# ARM_EURO_Platine7.net
KiCad netlist of a schematic drawn in Altium Designer
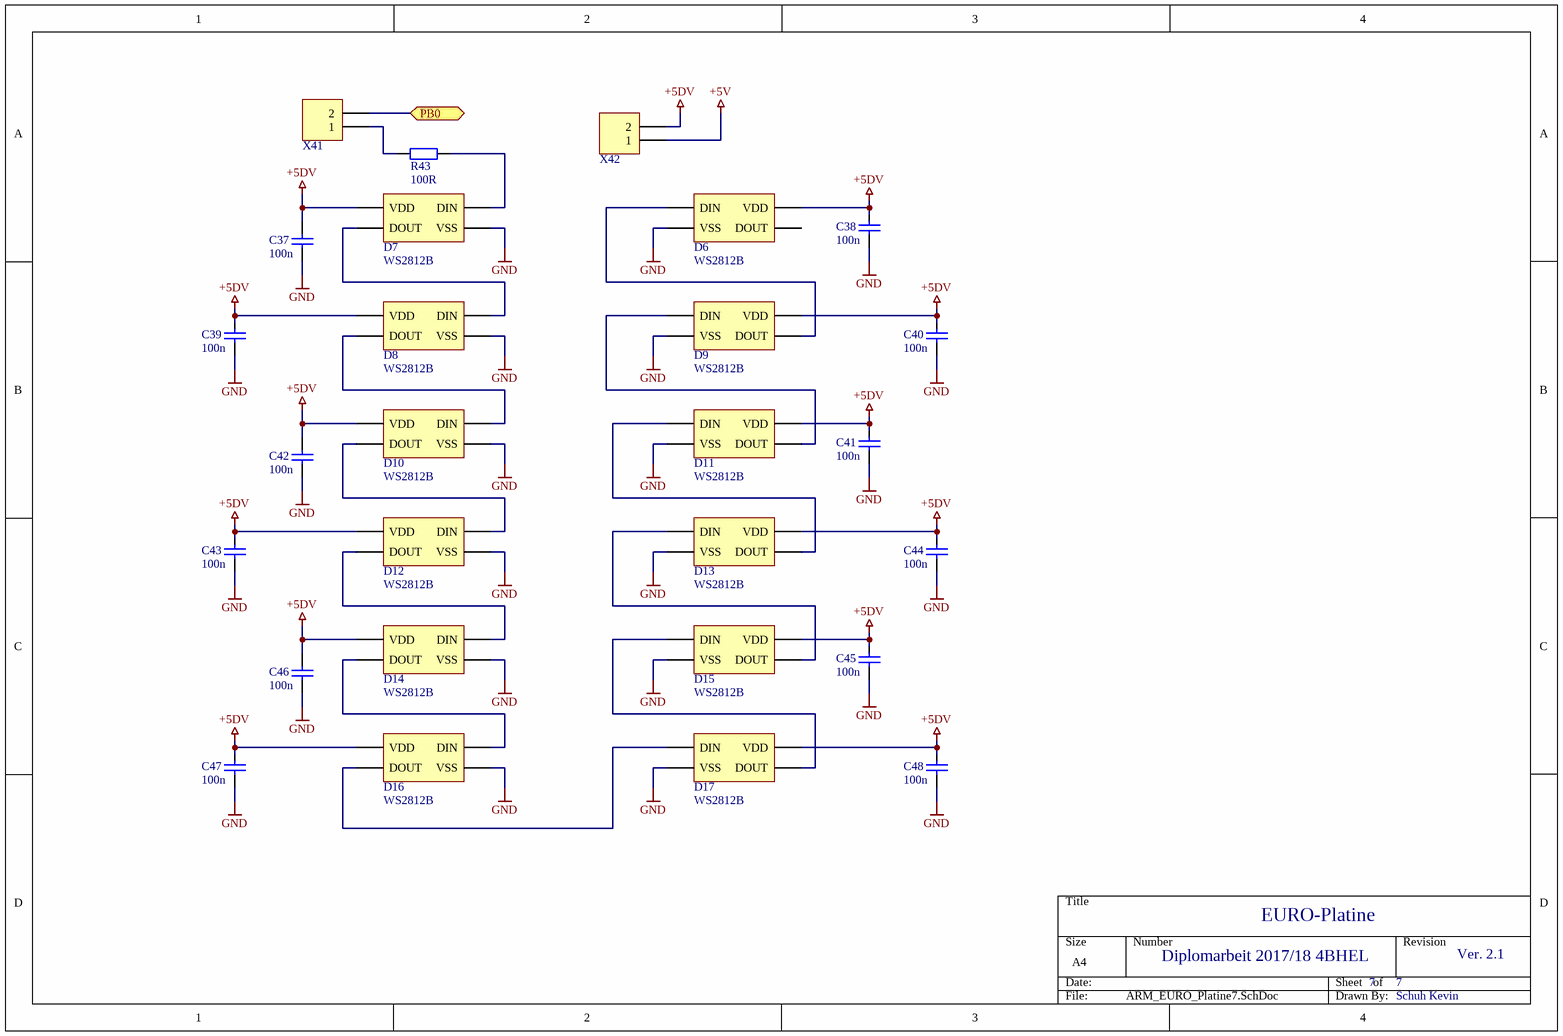
[diagram p0: ARM_EURO_Platine7.SchDoc]

(export (version "E")
  (design (tool "Eeschema 10.0.6"))
  (components
    (comp (ref "C37")
      (value "100n")
      (footprint "0805_CAP")
      (description "Capacitor_SMD")
      (fields (field (name "Comment") "Cap_Keramik_SMD") (field (name "PUBLISHER") "Altium Limited"))
      (libsource (lib "ARM_Libary_EURO") (part "Cap_Keramik_SMD"))
    )
    (comp (ref "C38")
      (value "100n")
      (footprint "0805_CAP")
      (description "Capacitor_SMD")
      (fields (field (name "Comment") "Cap_Keramik_SMD") (field (name "PUBLISHER") "Altium Limited"))
      (libsource (lib "ARM_Libary_EURO") (part "Cap_Keramik_SMD"))
    )
    (comp (ref "C39")
      (value "100n")
      (footprint "0805_CAP")
      (description "Capacitor_SMD")
      (fields (field (name "Comment") "Cap_Keramik_SMD") (field (name "PUBLISHER") "Altium Limited"))
      (libsource (lib "ARM_Libary_EURO") (part "Cap_Keramik_SMD"))
    )
    (comp (ref "C40")
      (value "100n")
      (footprint "0805_CAP")
      (description "Capacitor_SMD")
      (fields (field (name "Comment") "Cap_Keramik_SMD") (field (name "PUBLISHER") "Altium Limited"))
      (libsource (lib "ARM_Libary_EURO") (part "Cap_Keramik_SMD"))
    )
    (comp (ref "C41")
      (value "100n")
      (footprint "0805_CAP")
      (description "Capacitor_SMD")
      (fields (field (name "Comment") "Cap_Keramik_SMD") (field (name "PUBLISHER") "Altium Limited"))
      (libsource (lib "ARM_Libary_EURO") (part "Cap_Keramik_SMD"))
    )
    (comp (ref "C42")
      (value "100n")
      (footprint "0805_CAP")
      (description "Capacitor_SMD")
      (fields (field (name "Comment") "Cap_Keramik_SMD") (field (name "PUBLISHER") "Altium Limited"))
      (libsource (lib "ARM_Libary_EURO") (part "Cap_Keramik_SMD"))
    )
    (comp (ref "C43")
      (value "100n")
      (footprint "0805_CAP")
      (description "Capacitor_SMD")
      (fields (field (name "Comment") "Cap_Keramik_SMD") (field (name "PUBLISHER") "Altium Limited"))
      (libsource (lib "ARM_Libary_EURO") (part "Cap_Keramik_SMD"))
    )
    (comp (ref "C44")
      (value "100n")
      (footprint "0805_CAP")
      (description "Capacitor_SMD")
      (fields (field (name "Comment") "Cap_Keramik_SMD") (field (name "PUBLISHER") "Altium Limited"))
      (libsource (lib "ARM_Libary_EURO") (part "Cap_Keramik_SMD"))
    )
    (comp (ref "C45")
      (value "100n")
      (footprint "0805_CAP")
      (description "Capacitor_SMD")
      (fields (field (name "Comment") "Cap_Keramik_SMD") (field (name "PUBLISHER") "Altium Limited"))
      (libsource (lib "ARM_Libary_EURO") (part "Cap_Keramik_SMD"))
    )
    (comp (ref "C46")
      (value "100n")
      (footprint "0805_CAP")
      (description "Capacitor_SMD")
      (fields (field (name "Comment") "Cap_Keramik_SMD") (field (name "PUBLISHER") "Altium Limited"))
      (libsource (lib "ARM_Libary_EURO") (part "Cap_Keramik_SMD"))
    )
    (comp (ref "C47")
      (value "100n")
      (footprint "0805_CAP")
      (description "Capacitor_SMD")
      (fields (field (name "Comment") "Cap_Keramik_SMD") (field (name "PUBLISHER") "Altium Limited"))
      (libsource (lib "ARM_Libary_EURO") (part "Cap_Keramik_SMD"))
    )
    (comp (ref "C48")
      (value "100n")
      (footprint "0805_CAP")
      (description "Capacitor_SMD")
      (fields (field (name "Comment") "Cap_Keramik_SMD") (field (name "PUBLISHER") "Altium Limited"))
      (libsource (lib "ARM_Libary_EURO") (part "Cap_Keramik_SMD"))
    )
    (comp (ref "D6")
      (value "WS2812B")
      (footprint "WS2812B")
      (fields (field (name "PUBLISHER") "Altium Limited"))
      (libsource (lib "") (part "WS2812B_1"))
    )
    (comp (ref "D7")
      (value "WS2812B")
      (footprint "WS2812B")
      (fields (field (name "PUBLISHER") "Altium Limited"))
      (libsource (lib "ARM_Libary_EURO") (part "WS2812B"))
    )
    (comp (ref "D8")
      (value "WS2812B")
      (footprint "WS2812B")
      (fields (field (name "PUBLISHER") "Altium Limited"))
      (libsource (lib "ARM_Libary_EURO") (part "WS2812B"))
    )
    (comp (ref "D9")
      (value "WS2812B")
      (footprint "WS2812B")
      (fields (field (name "PUBLISHER") "Altium Limited"))
      (libsource (lib "") (part "WS2812B_1"))
    )
    (comp (ref "D10")
      (value "WS2812B")
      (footprint "WS2812B")
      (fields (field (name "PUBLISHER") "Altium Limited"))
      (libsource (lib "ARM_Libary_EURO") (part "WS2812B"))
    )
    (comp (ref "D11")
      (value "WS2812B")
      (footprint "WS2812B")
      (fields (field (name "PUBLISHER") "Altium Limited"))
      (libsource (lib "") (part "WS2812B_1"))
    )
    (comp (ref "D12")
      (value "WS2812B")
      (footprint "WS2812B")
      (fields (field (name "PUBLISHER") "Altium Limited"))
      (libsource (lib "ARM_Libary_EURO") (part "WS2812B"))
    )
    (comp (ref "D13")
      (value "WS2812B")
      (footprint "WS2812B")
      (fields (field (name "PUBLISHER") "Altium Limited"))
      (libsource (lib "") (part "WS2812B_1"))
    )
    (comp (ref "D14")
      (value "WS2812B")
      (footprint "WS2812B")
      (fields (field (name "PUBLISHER") "Altium Limited"))
      (libsource (lib "ARM_Libary_EURO") (part "WS2812B"))
    )
    (comp (ref "D15")
      (value "WS2812B")
      (footprint "WS2812B")
      (fields (field (name "PUBLISHER") "Altium Limited"))
      (libsource (lib "") (part "WS2812B_1"))
    )
    (comp (ref "D16")
      (value "WS2812B")
      (footprint "WS2812B")
      (fields (field (name "PUBLISHER") "Altium Limited"))
      (libsource (lib "ARM_Libary_EURO") (part "WS2812B"))
    )
    (comp (ref "D17")
      (value "WS2812B")
      (footprint "WS2812B")
      (fields (field (name "PUBLISHER") "Altium Limited"))
      (libsource (lib "") (part "WS2812B_1"))
    )
    (comp (ref "R43")
      (value "100R")
      (footprint "0805_Res")
      (description "Resistor")
      (fields (field (name "Comment") "Res_SMD") (field (name "PUBLISHER") "Altium Limited"))
      (libsource (lib "ARM_Libary_EURO") (part "Res_SMD"))
    )
    (comp (ref "X41")
      (value "Header")
      (footprint "HDR1X2")
      (description "Header, 2-Pin")
      (fields (field (name "PUBLISHER") "Altium Limited"))
      (libsource (lib "ARM_Libary_EURO") (part "Header_2"))
    )
    (comp (ref "X42")
      (value "Header")
      (footprint "HDR1X2")
      (description "Header, 2-Pin")
      (fields (field (name "PUBLISHER") "Altium Limited"))
      (libsource (lib "ARM_Libary_EURO") (part "Header_2"))
    )
  )
  (nets
    (net (code "1") (name "+5DV") (class "Default")
      (node (ref "C37") (pin "2") (pinfunction "2_2") (pintype "passive"))
      (node (ref "C38") (pin "2") (pinfunction "2_2") (pintype "passive"))
      (node (ref "C39") (pin "2") (pinfunction "2_2") (pintype "passive"))
      (node (ref "C40") (pin "2") (pinfunction "2_2") (pintype "passive"))
      (node (ref "C41") (pin "2") (pinfunction "2_2") (pintype "passive"))
      (node (ref "C42") (pin "2") (pinfunction "2_2") (pintype "passive"))
      (node (ref "C43") (pin "2") (pinfunction "2_2") (pintype "passive"))
      (node (ref "C44") (pin "2") (pinfunction "2_2") (pintype "passive"))
      (node (ref "C45") (pin "2") (pinfunction "2_2") (pintype "passive"))
      (node (ref "C46") (pin "2") (pinfunction "2_2") (pintype "passive"))
      (node (ref "C47") (pin "2") (pinfunction "2_2") (pintype "passive"))
      (node (ref "C48") (pin "2") (pinfunction "2_2") (pintype "passive"))
      (node (ref "D10") (pin "1") (pinfunction "VDD_1") (pintype "passive"))
      (node (ref "D11") (pin "1") (pinfunction "VDD_1") (pintype "passive"))
      (node (ref "D12") (pin "1") (pinfunction "VDD_1") (pintype "passive"))
      (node (ref "D13") (pin "1") (pinfunction "VDD_1") (pintype "passive"))
      (node (ref "D14") (pin "1") (pinfunction "VDD_1") (pintype "passive"))
      (node (ref "D15") (pin "1") (pinfunction "VDD_1") (pintype "passive"))
      (node (ref "D16") (pin "1") (pinfunction "VDD_1") (pintype "passive"))
      (node (ref "D17") (pin "1") (pinfunction "VDD_1") (pintype "passive"))
      (node (ref "D6") (pin "1") (pinfunction "VDD_1") (pintype "passive"))
      (node (ref "D7") (pin "1") (pinfunction "VDD_1") (pintype "passive"))
      (node (ref "D8") (pin "1") (pinfunction "VDD_1") (pintype "passive"))
      (node (ref "D9") (pin "1") (pinfunction "VDD_1") (pintype "passive"))
      (node (ref "X42") (pin "2") (pinfunction "2_2") (pintype "passive"))
    )
    (net (code "2") (name "+5V") (class "Default")
      (node (ref "X42") (pin "1") (pinfunction "1_1") (pintype "passive"))
    )
    (net (code "3") (name "/PB0") (class "Default")
      (node (ref "X41") (pin "2") (pinfunction "2_2") (pintype "passive"))
    )
    (net (code "4") (name "GND") (class "Default")
      (node (ref "C37") (pin "1") (pinfunction "1_1") (pintype "passive"))
      (node (ref "C38") (pin "1") (pinfunction "1_1") (pintype "passive"))
      (node (ref "C39") (pin "1") (pinfunction "1_1") (pintype "passive"))
      (node (ref "C40") (pin "1") (pinfunction "1_1") (pintype "passive"))
      (node (ref "C41") (pin "1") (pinfunction "1_1") (pintype "passive"))
      (node (ref "C42") (pin "1") (pinfunction "1_1") (pintype "passive"))
      (node (ref "C43") (pin "1") (pinfunction "1_1") (pintype "passive"))
      (node (ref "C44") (pin "1") (pinfunction "1_1") (pintype "passive"))
      (node (ref "C45") (pin "1") (pinfunction "1_1") (pintype "passive"))
      (node (ref "C46") (pin "1") (pinfunction "1_1") (pintype "passive"))
      (node (ref "C47") (pin "1") (pinfunction "1_1") (pintype "passive"))
      (node (ref "C48") (pin "1") (pinfunction "1_1") (pintype "passive"))
      (node (ref "D10") (pin "3") (pinfunction "VSS_3") (pintype "passive"))
      (node (ref "D11") (pin "3") (pinfunction "VSS_3") (pintype "passive"))
      (node (ref "D12") (pin "3") (pinfunction "VSS_3") (pintype "passive"))
      (node (ref "D13") (pin "3") (pinfunction "VSS_3") (pintype "passive"))
      (node (ref "D14") (pin "3") (pinfunction "VSS_3") (pintype "passive"))
      (node (ref "D15") (pin "3") (pinfunction "VSS_3") (pintype "passive"))
      (node (ref "D16") (pin "3") (pinfunction "VSS_3") (pintype "passive"))
      (node (ref "D17") (pin "3") (pinfunction "VSS_3") (pintype "passive"))
      (node (ref "D6") (pin "3") (pinfunction "VSS_3") (pintype "passive"))
      (node (ref "D7") (pin "3") (pinfunction "VSS_3") (pintype "passive"))
      (node (ref "D8") (pin "3") (pinfunction "VSS_3") (pintype "passive"))
      (node (ref "D9") (pin "3") (pinfunction "VSS_3") (pintype "passive"))
    )
    (net (code "5") (name "Net-(D6-DIN)") (class "Default")
      (node (ref "D6") (pin "4") (pinfunction "DIN_4") (pintype "passive"))
      (node (ref "D9") (pin "2") (pinfunction "DOUT_2") (pintype "passive"))
    )
    (net (code "6") (name "Net-(D7-DIN)") (class "Default")
      (node (ref "D7") (pin "4") (pinfunction "DIN_4") (pintype "passive"))
      (node (ref "R43") (pin "2") (pinfunction "2_2") (pintype "passive"))
    )
    (net (code "7") (name "Net-(D7-DOUT)") (class "Default")
      (node (ref "D7") (pin "2") (pinfunction "DOUT_2") (pintype "passive"))
      (node (ref "D8") (pin "4") (pinfunction "DIN_4") (pintype "passive"))
    )
    (net (code "8") (name "Net-(D10-DIN)") (class "Default")
      (node (ref "D10") (pin "4") (pinfunction "DIN_4") (pintype "passive"))
      (node (ref "D8") (pin "2") (pinfunction "DOUT_2") (pintype "passive"))
    )
    (net (code "9") (name "Net-(D10-DOUT)") (class "Default")
      (node (ref "D10") (pin "2") (pinfunction "DOUT_2") (pintype "passive"))
      (node (ref "D12") (pin "4") (pinfunction "DIN_4") (pintype "passive"))
    )
    (net (code "10") (name "Net-(D11-DIN)") (class "Default")
      (node (ref "D11") (pin "4") (pinfunction "DIN_4") (pintype "passive"))
      (node (ref "D13") (pin "2") (pinfunction "DOUT_2") (pintype "passive"))
    )
    (net (code "11") (name "Net-(D11-DOUT)") (class "Default")
      (node (ref "D11") (pin "2") (pinfunction "DOUT_2") (pintype "passive"))
      (node (ref "D9") (pin "4") (pinfunction "DIN_4") (pintype "passive"))
    )
    (net (code "12") (name "Net-(D12-DOUT)") (class "Default")
      (node (ref "D12") (pin "2") (pinfunction "DOUT_2") (pintype "passive"))
      (node (ref "D14") (pin "4") (pinfunction "DIN_4") (pintype "passive"))
    )
    (net (code "13") (name "Net-(D13-DIN)") (class "Default")
      (node (ref "D13") (pin "4") (pinfunction "DIN_4") (pintype "passive"))
      (node (ref "D15") (pin "2") (pinfunction "DOUT_2") (pintype "passive"))
    )
    (net (code "14") (name "Net-(D14-DOUT)") (class "Default")
      (node (ref "D14") (pin "2") (pinfunction "DOUT_2") (pintype "passive"))
      (node (ref "D16") (pin "4") (pinfunction "DIN_4") (pintype "passive"))
    )
    (net (code "15") (name "Net-(D15-DIN)") (class "Default")
      (node (ref "D15") (pin "4") (pinfunction "DIN_4") (pintype "passive"))
      (node (ref "D17") (pin "2") (pinfunction "DOUT_2") (pintype "passive"))
    )
    (net (code "16") (name "Net-(D16-DOUT)") (class "Default")
      (node (ref "D16") (pin "2") (pinfunction "DOUT_2") (pintype "passive"))
      (node (ref "D17") (pin "4") (pinfunction "DIN_4") (pintype "passive"))
    )
    (net (code "17") (name "Net-(R43-Pad1)") (class "Default")
      (node (ref "R43") (pin "1") (pinfunction "1_1") (pintype "passive"))
      (node (ref "X41") (pin "1") (pinfunction "1_1") (pintype "passive"))
    )
    (net (code "18") (name "unconnected-(D6-DOUT-Pad2)") (class "Default")
      (node (ref "D6") (pin "2") (pinfunction "DOUT_2") (pintype "passive"))
    )
  )
)
